# ArduinoPiano.net
KiCad netlist of a schematic drawn in EAGLE
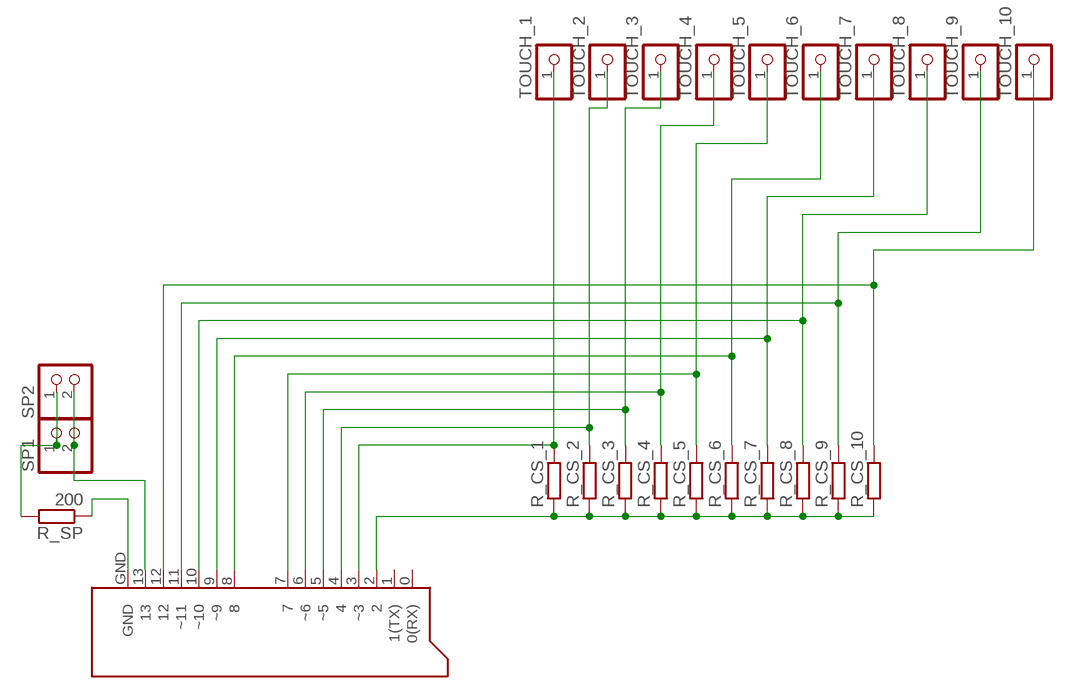
[diagram p0: schematic, sheet 1]

(export (version "E")
  (design (tool "Eeschema 10.0.6"))
  (components
    (comp (ref "PCB1")
      (value "ARDUINO_UNO")
      (footprint "eagle-import:ARDUINO_UNO")
      (libsource (lib "eagle-import") (part "ARDUINO_UNO"))
    )
    (comp (ref "R_CS_1")
      (value "R-EU_0204/7")
      (footprint "eagle-import:0204_7")
      (libsource (lib "eagle-import") (part "R-EU_0204/7"))
    )
    (comp (ref "R_CS_2")
      (value "R-EU_0204/7")
      (footprint "eagle-import:0204_7")
      (libsource (lib "eagle-import") (part "R-EU_0204/7"))
    )
    (comp (ref "R_CS_3")
      (value "R-EU_0204/7")
      (footprint "eagle-import:0204_7")
      (libsource (lib "eagle-import") (part "R-EU_0204/7"))
    )
    (comp (ref "R_CS_4")
      (value "R-EU_0204/7")
      (footprint "eagle-import:0204_7")
      (libsource (lib "eagle-import") (part "R-EU_0204/7"))
    )
    (comp (ref "R_CS_5")
      (value "R-EU_0204/7")
      (footprint "eagle-import:0204_7")
      (libsource (lib "eagle-import") (part "R-EU_0204/7"))
    )
    (comp (ref "R_CS_6")
      (value "R-EU_0204/7")
      (footprint "eagle-import:0204_7")
      (libsource (lib "eagle-import") (part "R-EU_0204/7"))
    )
    (comp (ref "R_CS_7")
      (value "R-EU_0204/7")
      (footprint "eagle-import:0204_7")
      (libsource (lib "eagle-import") (part "R-EU_0204/7"))
    )
    (comp (ref "R_CS_8")
      (value "R-EU_0204/7")
      (footprint "eagle-import:0204_7")
      (libsource (lib "eagle-import") (part "R-EU_0204/7"))
    )
    (comp (ref "R_CS_9")
      (value "R-EU_0204/7")
      (footprint "eagle-import:0204_7")
      (libsource (lib "eagle-import") (part "R-EU_0204/7"))
    )
    (comp (ref "R_CS_10")
      (value "R-EU_0204/7")
      (footprint "eagle-import:0204_7")
      (libsource (lib "eagle-import") (part "R-EU_0204/7"))
    )
    (comp (ref "R_SP")
      (value "200")
      (footprint "eagle-import:0204_7")
      (libsource (lib "eagle-import") (part "R-EU_0204/7"))
    )
    (comp (ref "SP1")
      (value "PINHD-1X2")
      (footprint "eagle-import:1X02")
      (libsource (lib "eagle-import") (part "PINHD-1X2"))
    )
    (comp (ref "SP2")
      (value "PINHD-1X2")
      (footprint "eagle-import:1X02")
      (libsource (lib "eagle-import") (part "PINHD-1X2"))
    )
    (comp (ref "TOUCH_1")
      (value "PINHD-1X1")
      (footprint "eagle-import:1X01")
      (libsource (lib "eagle-import") (part "PINHD-1X1"))
    )
    (comp (ref "TOUCH_2")
      (value "PINHD-1X1")
      (footprint "eagle-import:1X01")
      (libsource (lib "eagle-import") (part "PINHD-1X1"))
    )
    (comp (ref "TOUCH_3")
      (value "PINHD-1X1")
      (footprint "eagle-import:1X01")
      (libsource (lib "eagle-import") (part "PINHD-1X1"))
    )
    (comp (ref "TOUCH_4")
      (value "PINHD-1X1")
      (footprint "eagle-import:1X01")
      (libsource (lib "eagle-import") (part "PINHD-1X1"))
    )
    (comp (ref "TOUCH_5")
      (value "PINHD-1X1")
      (footprint "eagle-import:1X01")
      (libsource (lib "eagle-import") (part "PINHD-1X1"))
    )
    (comp (ref "TOUCH_6")
      (value "PINHD-1X1")
      (footprint "eagle-import:1X01")
      (libsource (lib "eagle-import") (part "PINHD-1X1"))
    )
    (comp (ref "TOUCH_7")
      (value "PINHD-1X1")
      (footprint "eagle-import:1X01")
      (libsource (lib "eagle-import") (part "PINHD-1X1"))
    )
    (comp (ref "TOUCH_8")
      (value "PINHD-1X1")
      (footprint "eagle-import:1X01")
      (libsource (lib "eagle-import") (part "PINHD-1X1"))
    )
    (comp (ref "TOUCH_9")
      (value "PINHD-1X1")
      (footprint "eagle-import:1X01")
      (libsource (lib "eagle-import") (part "PINHD-1X1"))
    )
    (comp (ref "TOUCH_10")
      (value "PINHD-1X1")
      (footprint "eagle-import:1X01")
      (libsource (lib "eagle-import") (part "PINHD-1X1"))
    )
  )
  (nets
    (net (code "1") (name "Net-(PCB1-Pad2)") (class "Default")
      (node (ref "PCB1") (pin "2") (pinfunction "2_2") (pintype "bidirectional"))
      (node (ref "R_CS_1") (pin "1") (pinfunction "1_1") (pintype "passive"))
      (node (ref "R_CS_10") (pin "1") (pinfunction "1_1") (pintype "passive"))
      (node (ref "R_CS_2") (pin "1") (pinfunction "1_1") (pintype "passive"))
      (node (ref "R_CS_3") (pin "1") (pinfunction "1_1") (pintype "passive"))
      (node (ref "R_CS_4") (pin "1") (pinfunction "1_1") (pintype "passive"))
      (node (ref "R_CS_5") (pin "1") (pinfunction "1_1") (pintype "passive"))
      (node (ref "R_CS_6") (pin "1") (pinfunction "1_1") (pintype "passive"))
      (node (ref "R_CS_7") (pin "1") (pinfunction "1_1") (pintype "passive"))
      (node (ref "R_CS_8") (pin "1") (pinfunction "1_1") (pintype "passive"))
      (node (ref "R_CS_9") (pin "1") (pinfunction "1_1") (pintype "passive"))
    )
    (net (code "2") (name "Net-(PCB1-Pad4)") (class "Default")
      (node (ref "PCB1") (pin "4") (pinfunction "4_4") (pintype "bidirectional"))
      (node (ref "R_CS_2") (pin "2") (pinfunction "2_2") (pintype "passive"))
      (node (ref "TOUCH_2") (pin "1") (pinfunction "1_1") (pintype "passive"))
    )
    (net (code "3") (name "Net-(PCB1-Pad7)") (class "Default")
      (node (ref "PCB1") (pin "7") (pinfunction "7_7") (pintype "bidirectional"))
      (node (ref "R_CS_5") (pin "2") (pinfunction "2_2") (pintype "passive"))
      (node (ref "TOUCH_5") (pin "1") (pinfunction "1_1") (pintype "passive"))
    )
    (net (code "4") (name "Net-(PCB1-Pad8)") (class "Default")
      (node (ref "PCB1") (pin "8") (pinfunction "8_8") (pintype "bidirectional"))
      (node (ref "R_CS_6") (pin "2") (pinfunction "2_2") (pintype "passive"))
      (node (ref "TOUCH_6") (pin "1") (pinfunction "1_1") (pintype "passive"))
    )
    (net (code "5") (name "Net-(PCB1-Pad12)") (class "Default")
      (node (ref "PCB1") (pin "12") (pinfunction "12_12") (pintype "bidirectional"))
      (node (ref "R_CS_10") (pin "2") (pinfunction "2_2") (pintype "passive"))
      (node (ref "TOUCH_10") (pin "1") (pinfunction "1_1") (pintype "passive"))
    )
    (net (code "6") (name "Net-(PCB1-Pad13)") (class "Default")
      (node (ref "PCB1") (pin "13") (pinfunction "13_13") (pintype "bidirectional"))
      (node (ref "SP1") (pin "2") (pinfunction "2_2") (pintype "passive"))
      (node (ref "SP2") (pin "2") (pinfunction "2_2") (pintype "passive"))
    )
    (net (code "7") (name "Net-(PCB1-PadGND)") (class "Default")
      (node (ref "PCB1") (pin "GND") (pinfunction "GND_GND") (pintype "bidirectional"))
      (node (ref "R_SP") (pin "1") (pinfunction "1_1") (pintype "passive"))
    )
    (net (code "8") (name "Net-(PCB1-~{3})") (class "Default")
      (node (ref "PCB1") (pin "3") (pinfunction "~{3}_3") (pintype "bidirectional"))
      (node (ref "R_CS_1") (pin "2") (pinfunction "2_2") (pintype "passive"))
      (node (ref "TOUCH_1") (pin "1") (pinfunction "1_1") (pintype "passive"))
    )
    (net (code "9") (name "Net-(PCB1-~{5})") (class "Default")
      (node (ref "PCB1") (pin "5") (pinfunction "~{5}_5") (pintype "bidirectional"))
      (node (ref "R_CS_3") (pin "2") (pinfunction "2_2") (pintype "passive"))
      (node (ref "TOUCH_3") (pin "1") (pinfunction "1_1") (pintype "passive"))
    )
    (net (code "10") (name "Net-(PCB1-~{6})") (class "Default")
      (node (ref "PCB1") (pin "6") (pinfunction "~{6}_6") (pintype "bidirectional"))
      (node (ref "R_CS_4") (pin "2") (pinfunction "2_2") (pintype "passive"))
      (node (ref "TOUCH_4") (pin "1") (pinfunction "1_1") (pintype "passive"))
    )
    (net (code "11") (name "Net-(PCB1-~{9})") (class "Default")
      (node (ref "PCB1") (pin "9") (pinfunction "~{9}_9") (pintype "bidirectional"))
      (node (ref "R_CS_7") (pin "2") (pinfunction "2_2") (pintype "passive"))
      (node (ref "TOUCH_7") (pin "1") (pinfunction "1_1") (pintype "passive"))
    )
    (net (code "12") (name "Net-(PCB1-~{10})") (class "Default")
      (node (ref "PCB1") (pin "10") (pinfunction "~{10}_10") (pintype "bidirectional"))
      (node (ref "R_CS_8") (pin "2") (pinfunction "2_2") (pintype "passive"))
      (node (ref "TOUCH_8") (pin "1") (pinfunction "1_1") (pintype "passive"))
    )
    (net (code "13") (name "Net-(PCB1-~{11})") (class "Default")
      (node (ref "PCB1") (pin "11") (pinfunction "~{11}_11") (pintype "bidirectional"))
      (node (ref "R_CS_9") (pin "2") (pinfunction "2_2") (pintype "passive"))
      (node (ref "TOUCH_9") (pin "1") (pinfunction "1_1") (pintype "passive"))
    )
    (net (code "14") (name "Net-(R_SP-Pad2)") (class "Default")
      (node (ref "R_SP") (pin "2") (pinfunction "2_2") (pintype "passive"))
      (node (ref "SP1") (pin "1") (pinfunction "1_1") (pintype "passive"))
      (node (ref "SP2") (pin "1") (pinfunction "1_1") (pintype "passive"))
    )
    (net (code "15") (name "unconnected-(PCB1-0(RX)-Pad0)") (class "Default")
      (node (ref "PCB1") (pin "0") (pinfunction "0(RX)_0") (pintype "bidirectional"))
    )
    (net (code "16") (name "unconnected-(PCB1-1(TX)-Pad1)") (class "Default")
      (node (ref "PCB1") (pin "1") (pinfunction "1(TX)_1") (pintype "bidirectional"))
    )
  )
)
